# hairpin-L-band.net
KiCad netlist of a schematic drawn in EAGLE
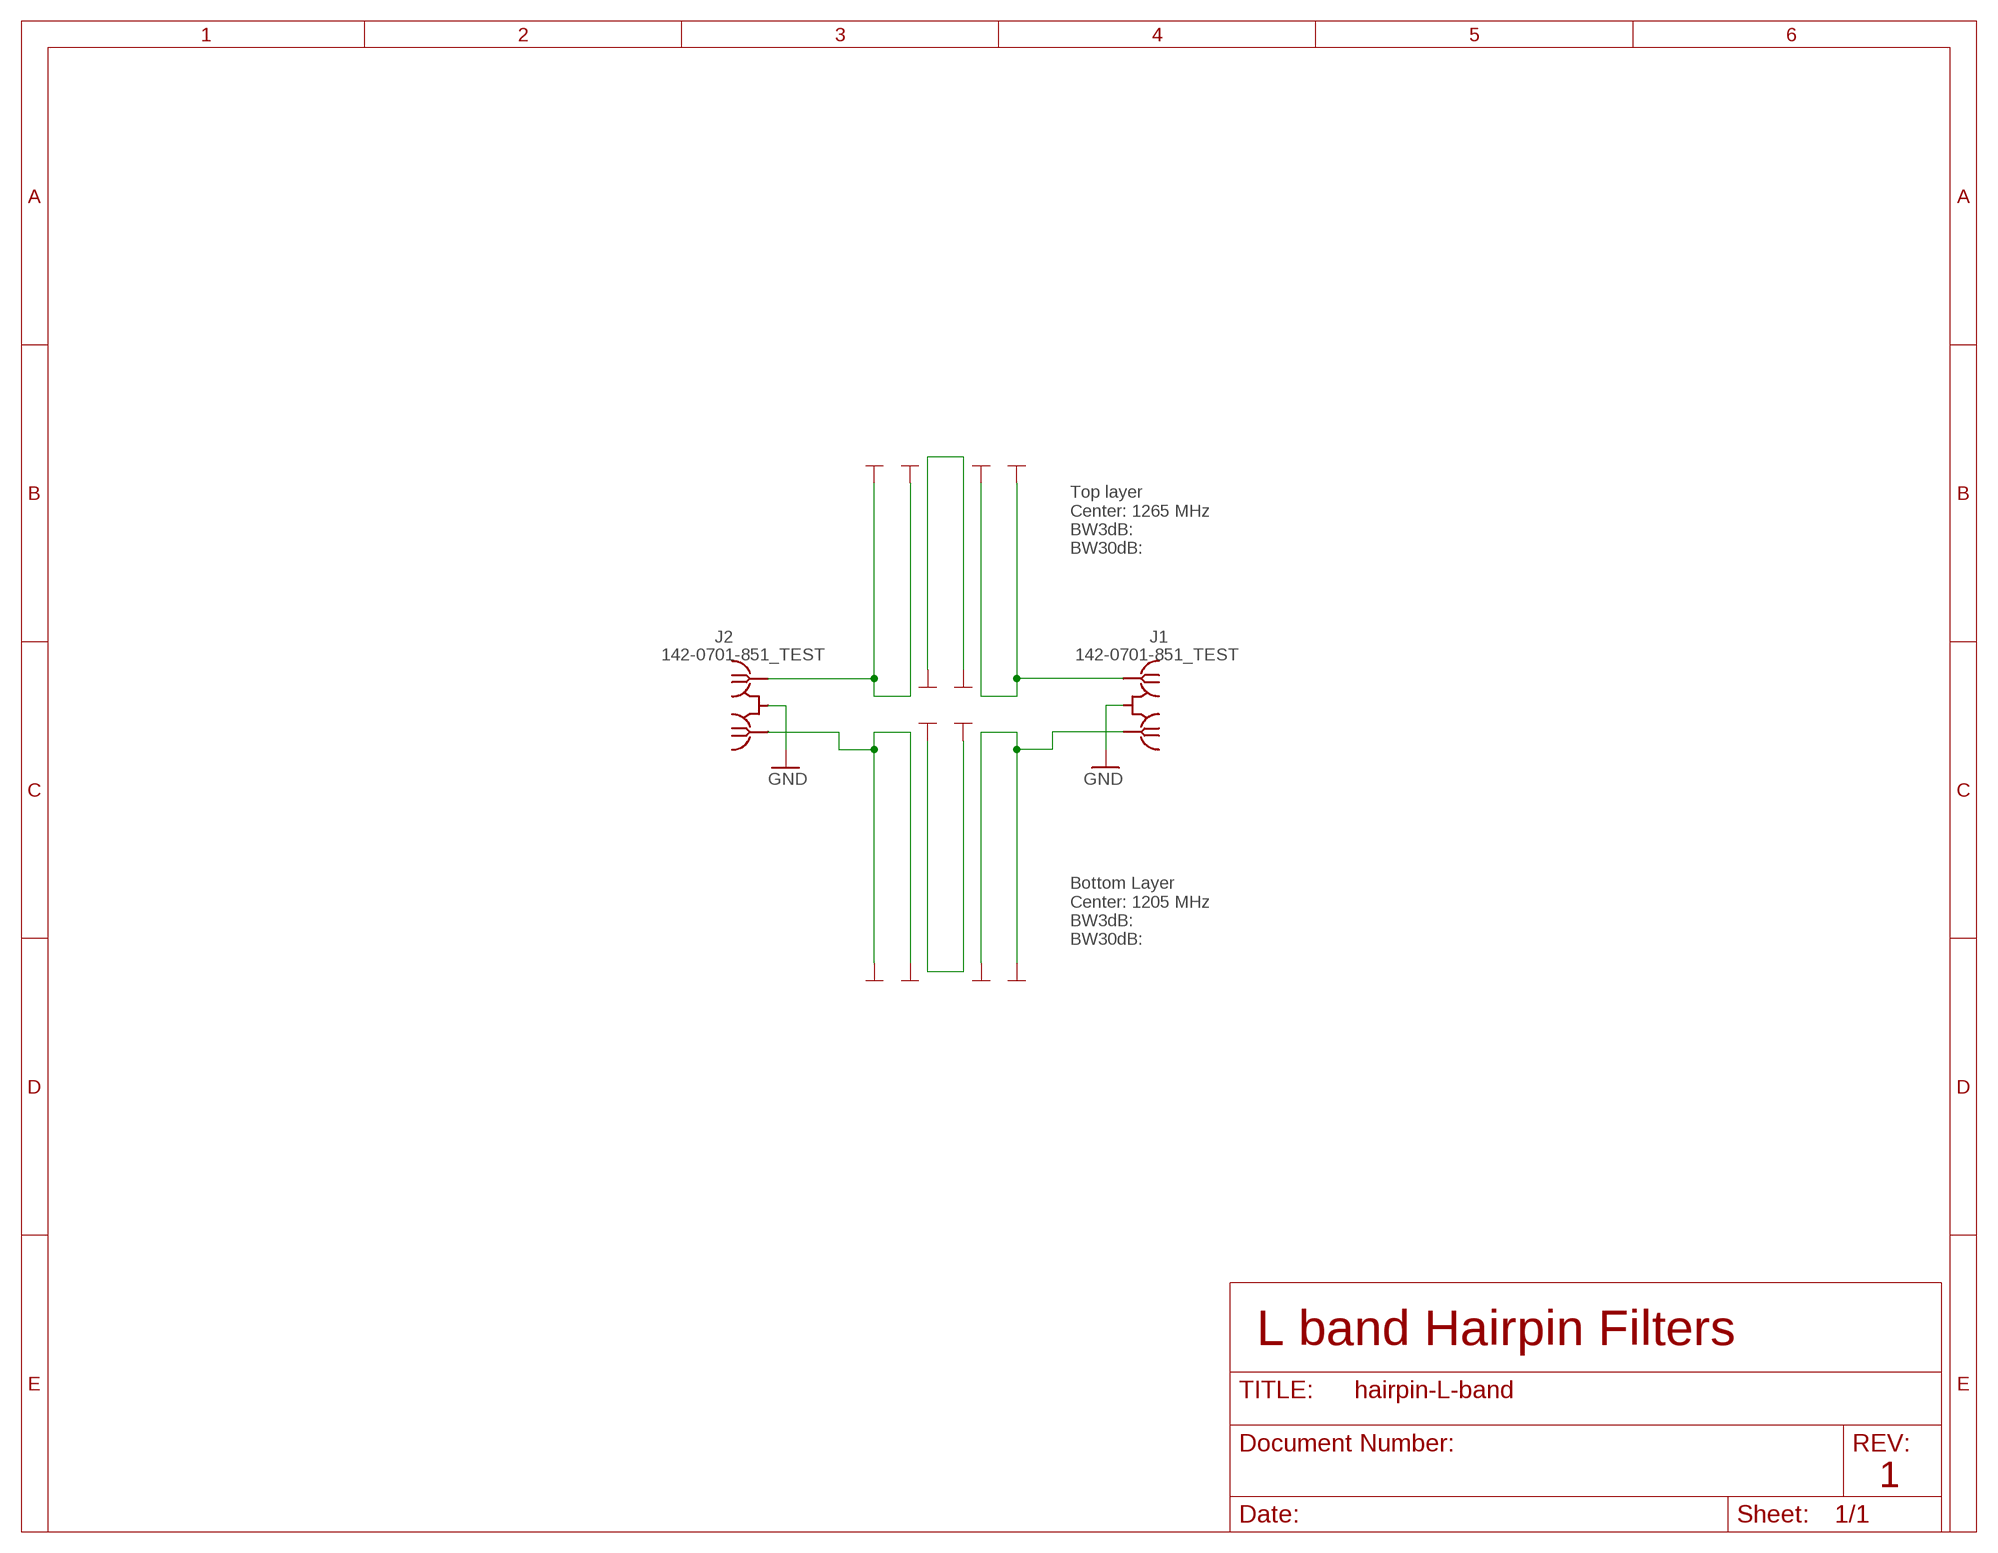
[diagram p0: schematic, sheet 1]

(export (version "E")
  (design (tool "Eeschema 10.0.6"))
  (components
    (comp (ref "J1")
      (value "142-0701-851_TEST")
      (footprint "eagle-import:142-0701-851_TEST")
      (libsource (lib "eagle-import") (part "142-0701-851_TEST"))
    )
    (comp (ref "J2")
      (value "142-0701-851_TEST")
      (footprint "eagle-import:142-0701-851_TEST")
      (libsource (lib "eagle-import") (part "142-0701-851_TEST"))
    )
    (comp (ref "U$1")
      (value "PAD_0.6")
      (footprint "eagle-import:0.6MM")
      (libsource (lib "eagle-import") (part "PAD_0.6"))
    )
    (comp (ref "U$2")
      (value "PAD_0.6")
      (footprint "eagle-import:0.6MM")
      (libsource (lib "eagle-import") (part "PAD_0.6"))
    )
    (comp (ref "U$3")
      (value "PAD_0.6")
      (footprint "eagle-import:0.6MM")
      (libsource (lib "eagle-import") (part "PAD_0.6"))
    )
    (comp (ref "U$4")
      (value "PAD_0.6")
      (footprint "eagle-import:0.6MM")
      (libsource (lib "eagle-import") (part "PAD_0.6"))
    )
    (comp (ref "U$5")
      (value "PAD_0.6")
      (footprint "eagle-import:0.6MM")
      (libsource (lib "eagle-import") (part "PAD_0.6"))
    )
    (comp (ref "U$6")
      (value "PAD_0.6")
      (footprint "eagle-import:0.6MM")
      (libsource (lib "eagle-import") (part "PAD_0.6"))
    )
    (comp (ref "U$7")
      (value "PAD_0.6_B")
      (footprint "eagle-import:0.6MM_B")
      (libsource (lib "eagle-import") (part "PAD_0.6_B"))
    )
    (comp (ref "U$8")
      (value "PAD_0.6_B")
      (footprint "eagle-import:0.6MM_B")
      (libsource (lib "eagle-import") (part "PAD_0.6_B"))
    )
    (comp (ref "U$9")
      (value "PAD_0.6_B")
      (footprint "eagle-import:0.6MM_B")
      (libsource (lib "eagle-import") (part "PAD_0.6_B"))
    )
    (comp (ref "U$10")
      (value "PAD_0.6_B")
      (footprint "eagle-import:0.6MM_B")
      (libsource (lib "eagle-import") (part "PAD_0.6_B"))
    )
    (comp (ref "U$11")
      (value "PAD_0.6_B")
      (footprint "eagle-import:0.6MM_B")
      (libsource (lib "eagle-import") (part "PAD_0.6_B"))
    )
    (comp (ref "U$12")
      (value "PAD_0.6_B")
      (footprint "eagle-import:0.6MM_B")
      (libsource (lib "eagle-import") (part "PAD_0.6_B"))
    )
  )
  (nets
    (net (code "1") (name "GND") (class "Default")
      (node (ref "J1") (pin "GND1") (pinfunction "GND_GND1") (pintype "bidirectional"))
      (node (ref "J1") (pin "GND2") (pinfunction "GND_GND2") (pintype "bidirectional"))
      (node (ref "J1") (pin "GND3") (pinfunction "GND_GND3") (pintype "bidirectional"))
      (node (ref "J1") (pin "GND4") (pinfunction "GND_GND4") (pintype "bidirectional"))
      (node (ref "J2") (pin "GND1") (pinfunction "GND_GND1") (pintype "bidirectional"))
      (node (ref "J2") (pin "GND2") (pinfunction "GND_GND2") (pintype "bidirectional"))
      (node (ref "J2") (pin "GND3") (pinfunction "GND_GND3") (pintype "bidirectional"))
      (node (ref "J2") (pin "GND4") (pinfunction "GND_GND4") (pintype "bidirectional"))
    )
    (net (code "2") (name "Net-(J1-PadRF1)") (class "Default")
      (node (ref "J1") (pin "RF1") (pinfunction "RF1_RF1") (pintype "bidirectional"))
      (node (ref "U$1") (pin "END") (pinfunction "END_END") (pintype "bidirectional"))
      (node (ref "U$2") (pin "END") (pinfunction "END_END") (pintype "bidirectional"))
    )
    (net (code "3") (name "Net-(J1-PadRF2)") (class "Default")
      (node (ref "J1") (pin "RF2") (pinfunction "RF2_RF2") (pintype "bidirectional"))
      (node (ref "U$7") (pin "END") (pinfunction "END_END") (pintype "bidirectional"))
      (node (ref "U$8") (pin "END") (pinfunction "END_END") (pintype "bidirectional"))
    )
    (net (code "4") (name "Net-(J2-PadRF1)") (class "Default")
      (node (ref "J2") (pin "RF1") (pinfunction "RF1_RF1") (pintype "bidirectional"))
      (node (ref "U$5") (pin "END") (pinfunction "END_END") (pintype "bidirectional"))
      (node (ref "U$6") (pin "END") (pinfunction "END_END") (pintype "bidirectional"))
    )
    (net (code "5") (name "Net-(J2-PadRF2)") (class "Default")
      (node (ref "J2") (pin "RF2") (pinfunction "RF2_RF2") (pintype "bidirectional"))
      (node (ref "U$11") (pin "END") (pinfunction "END_END") (pintype "bidirectional"))
      (node (ref "U$12") (pin "END") (pinfunction "END_END") (pintype "bidirectional"))
    )
    (net (code "6") (name "Net-(U$3-PadEND)") (class "Default")
      (node (ref "U$3") (pin "END") (pinfunction "END_END") (pintype "bidirectional"))
      (node (ref "U$4") (pin "END") (pinfunction "END_END") (pintype "bidirectional"))
    )
    (net (code "7") (name "Net-(U$10-PadEND)") (class "Default")
      (node (ref "U$10") (pin "END") (pinfunction "END_END") (pintype "bidirectional"))
      (node (ref "U$9") (pin "END") (pinfunction "END_END") (pintype "bidirectional"))
    )
  )
)
